# SCH_SmartOEEBoard_2023-07-03.net
KiCad netlist of a schematic drawn in EasyEDA
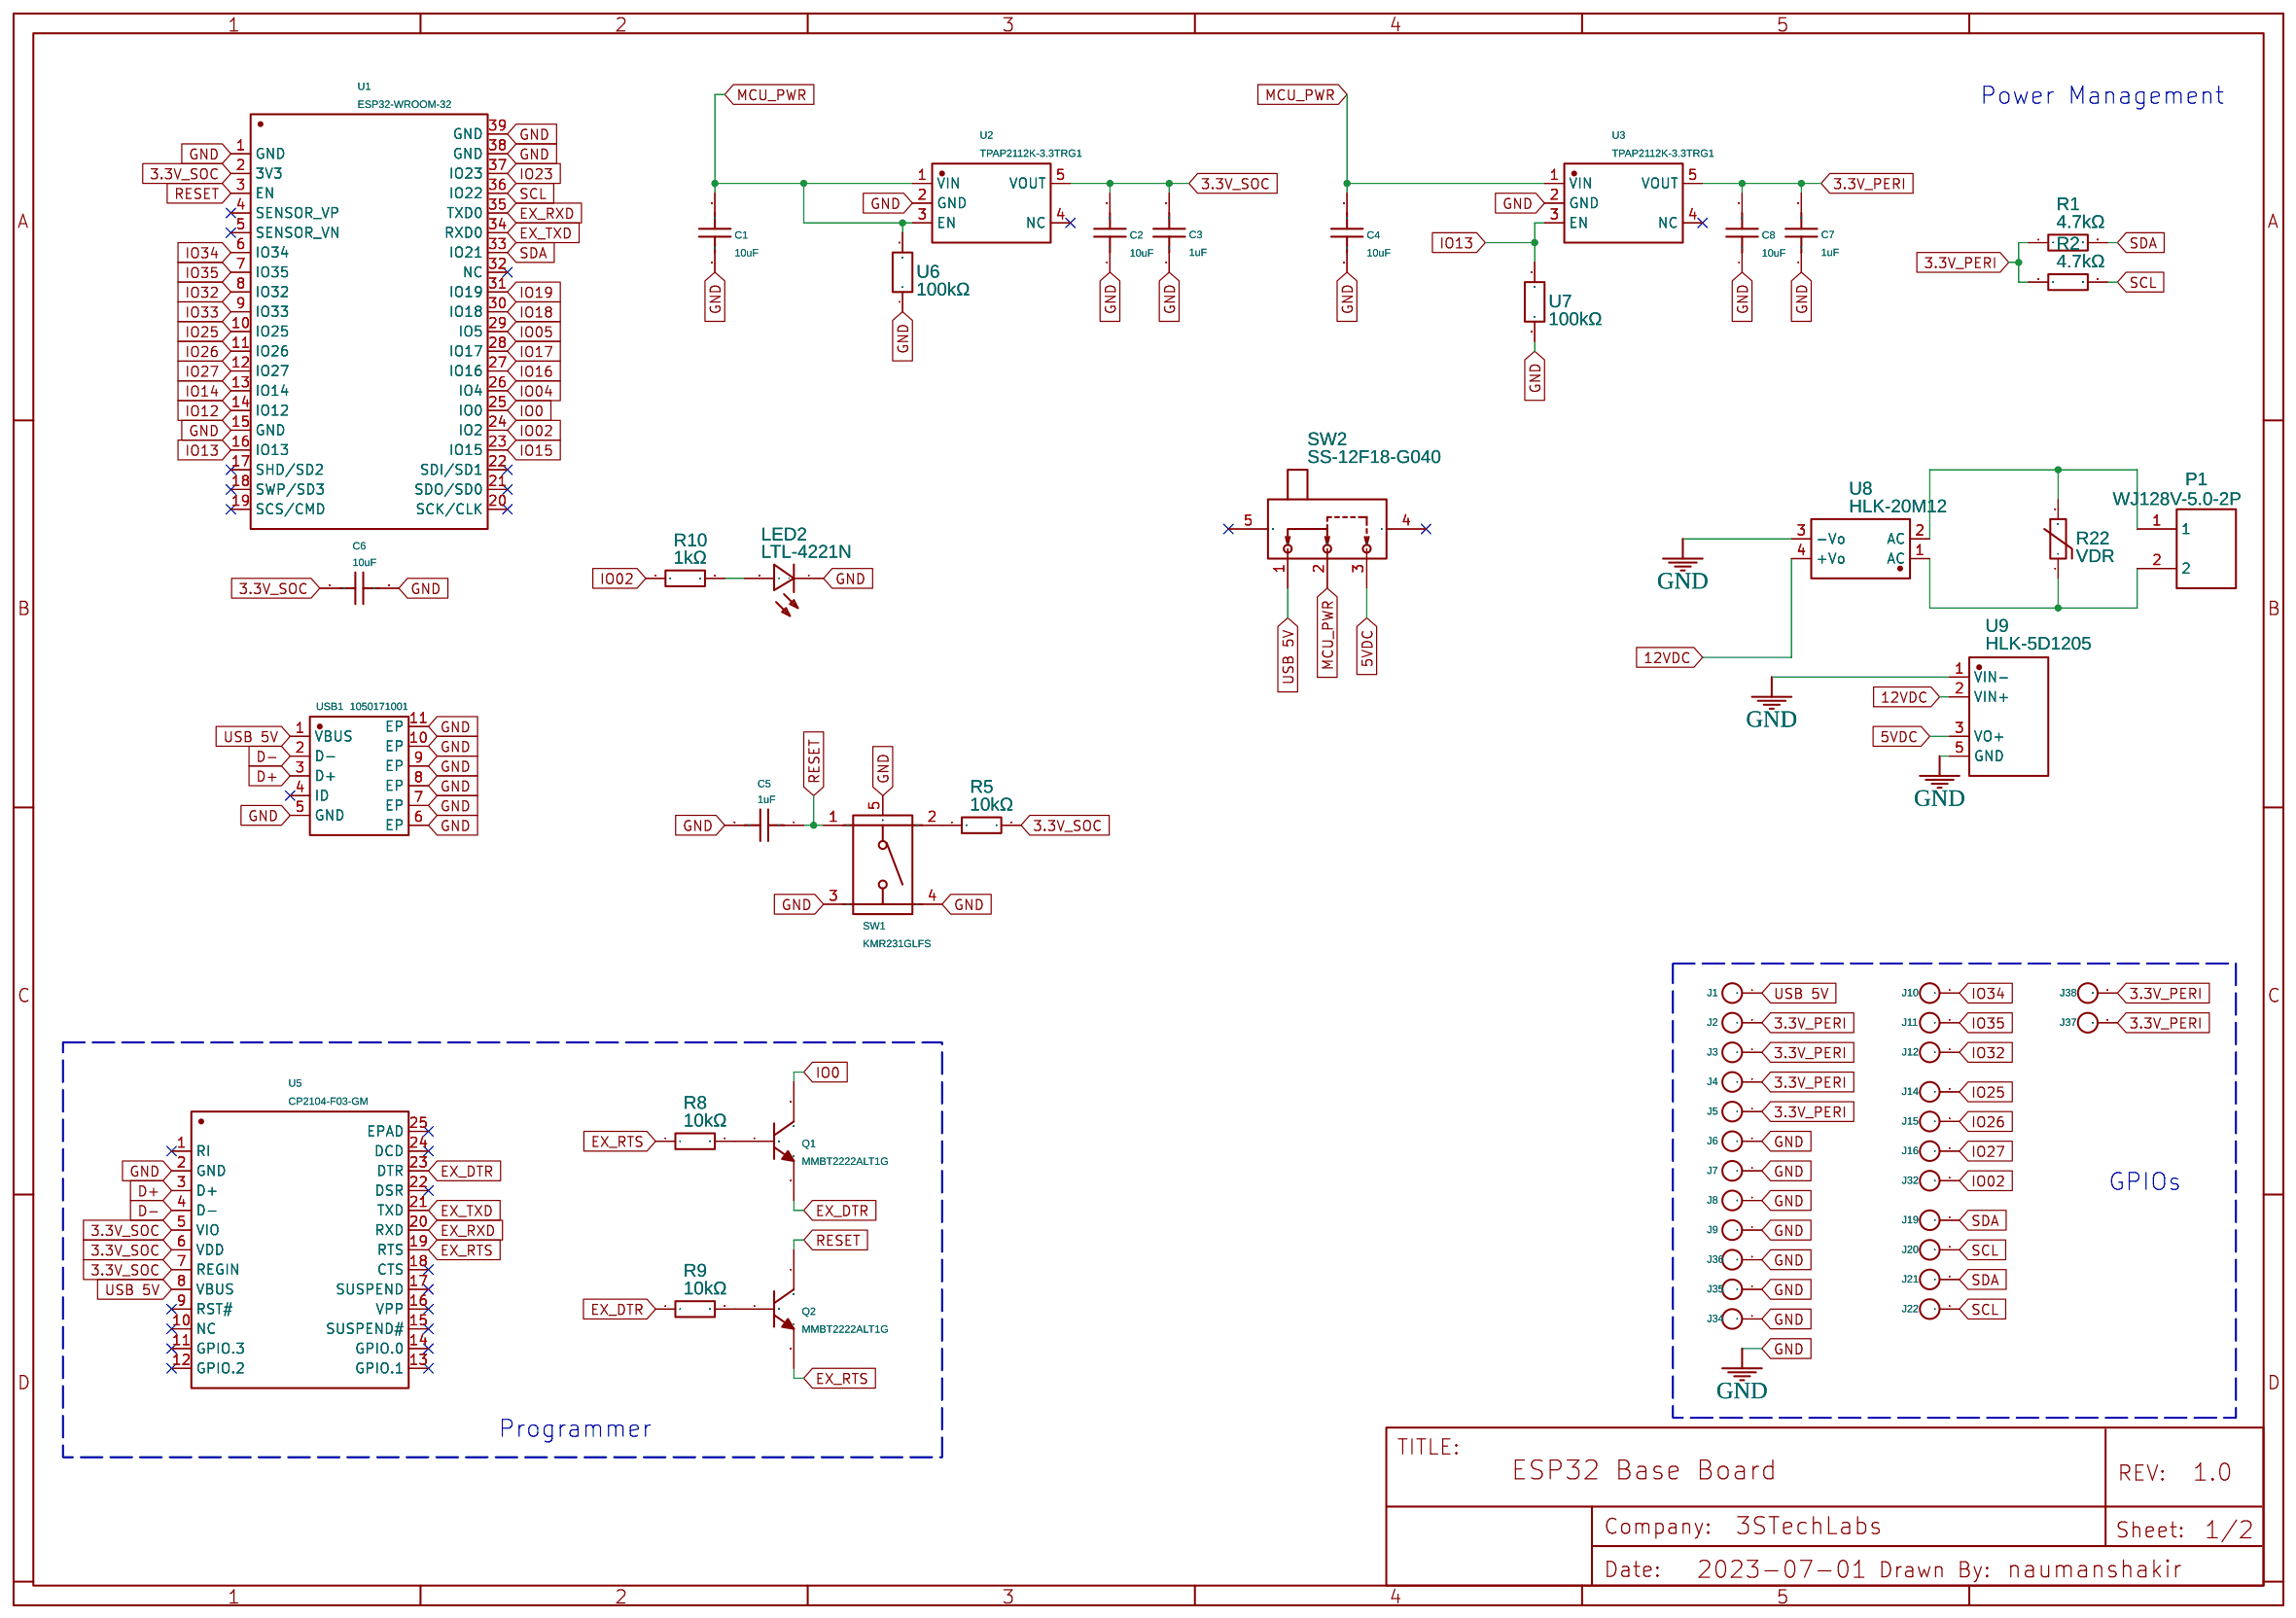
[diagram p0: Sheet_1]
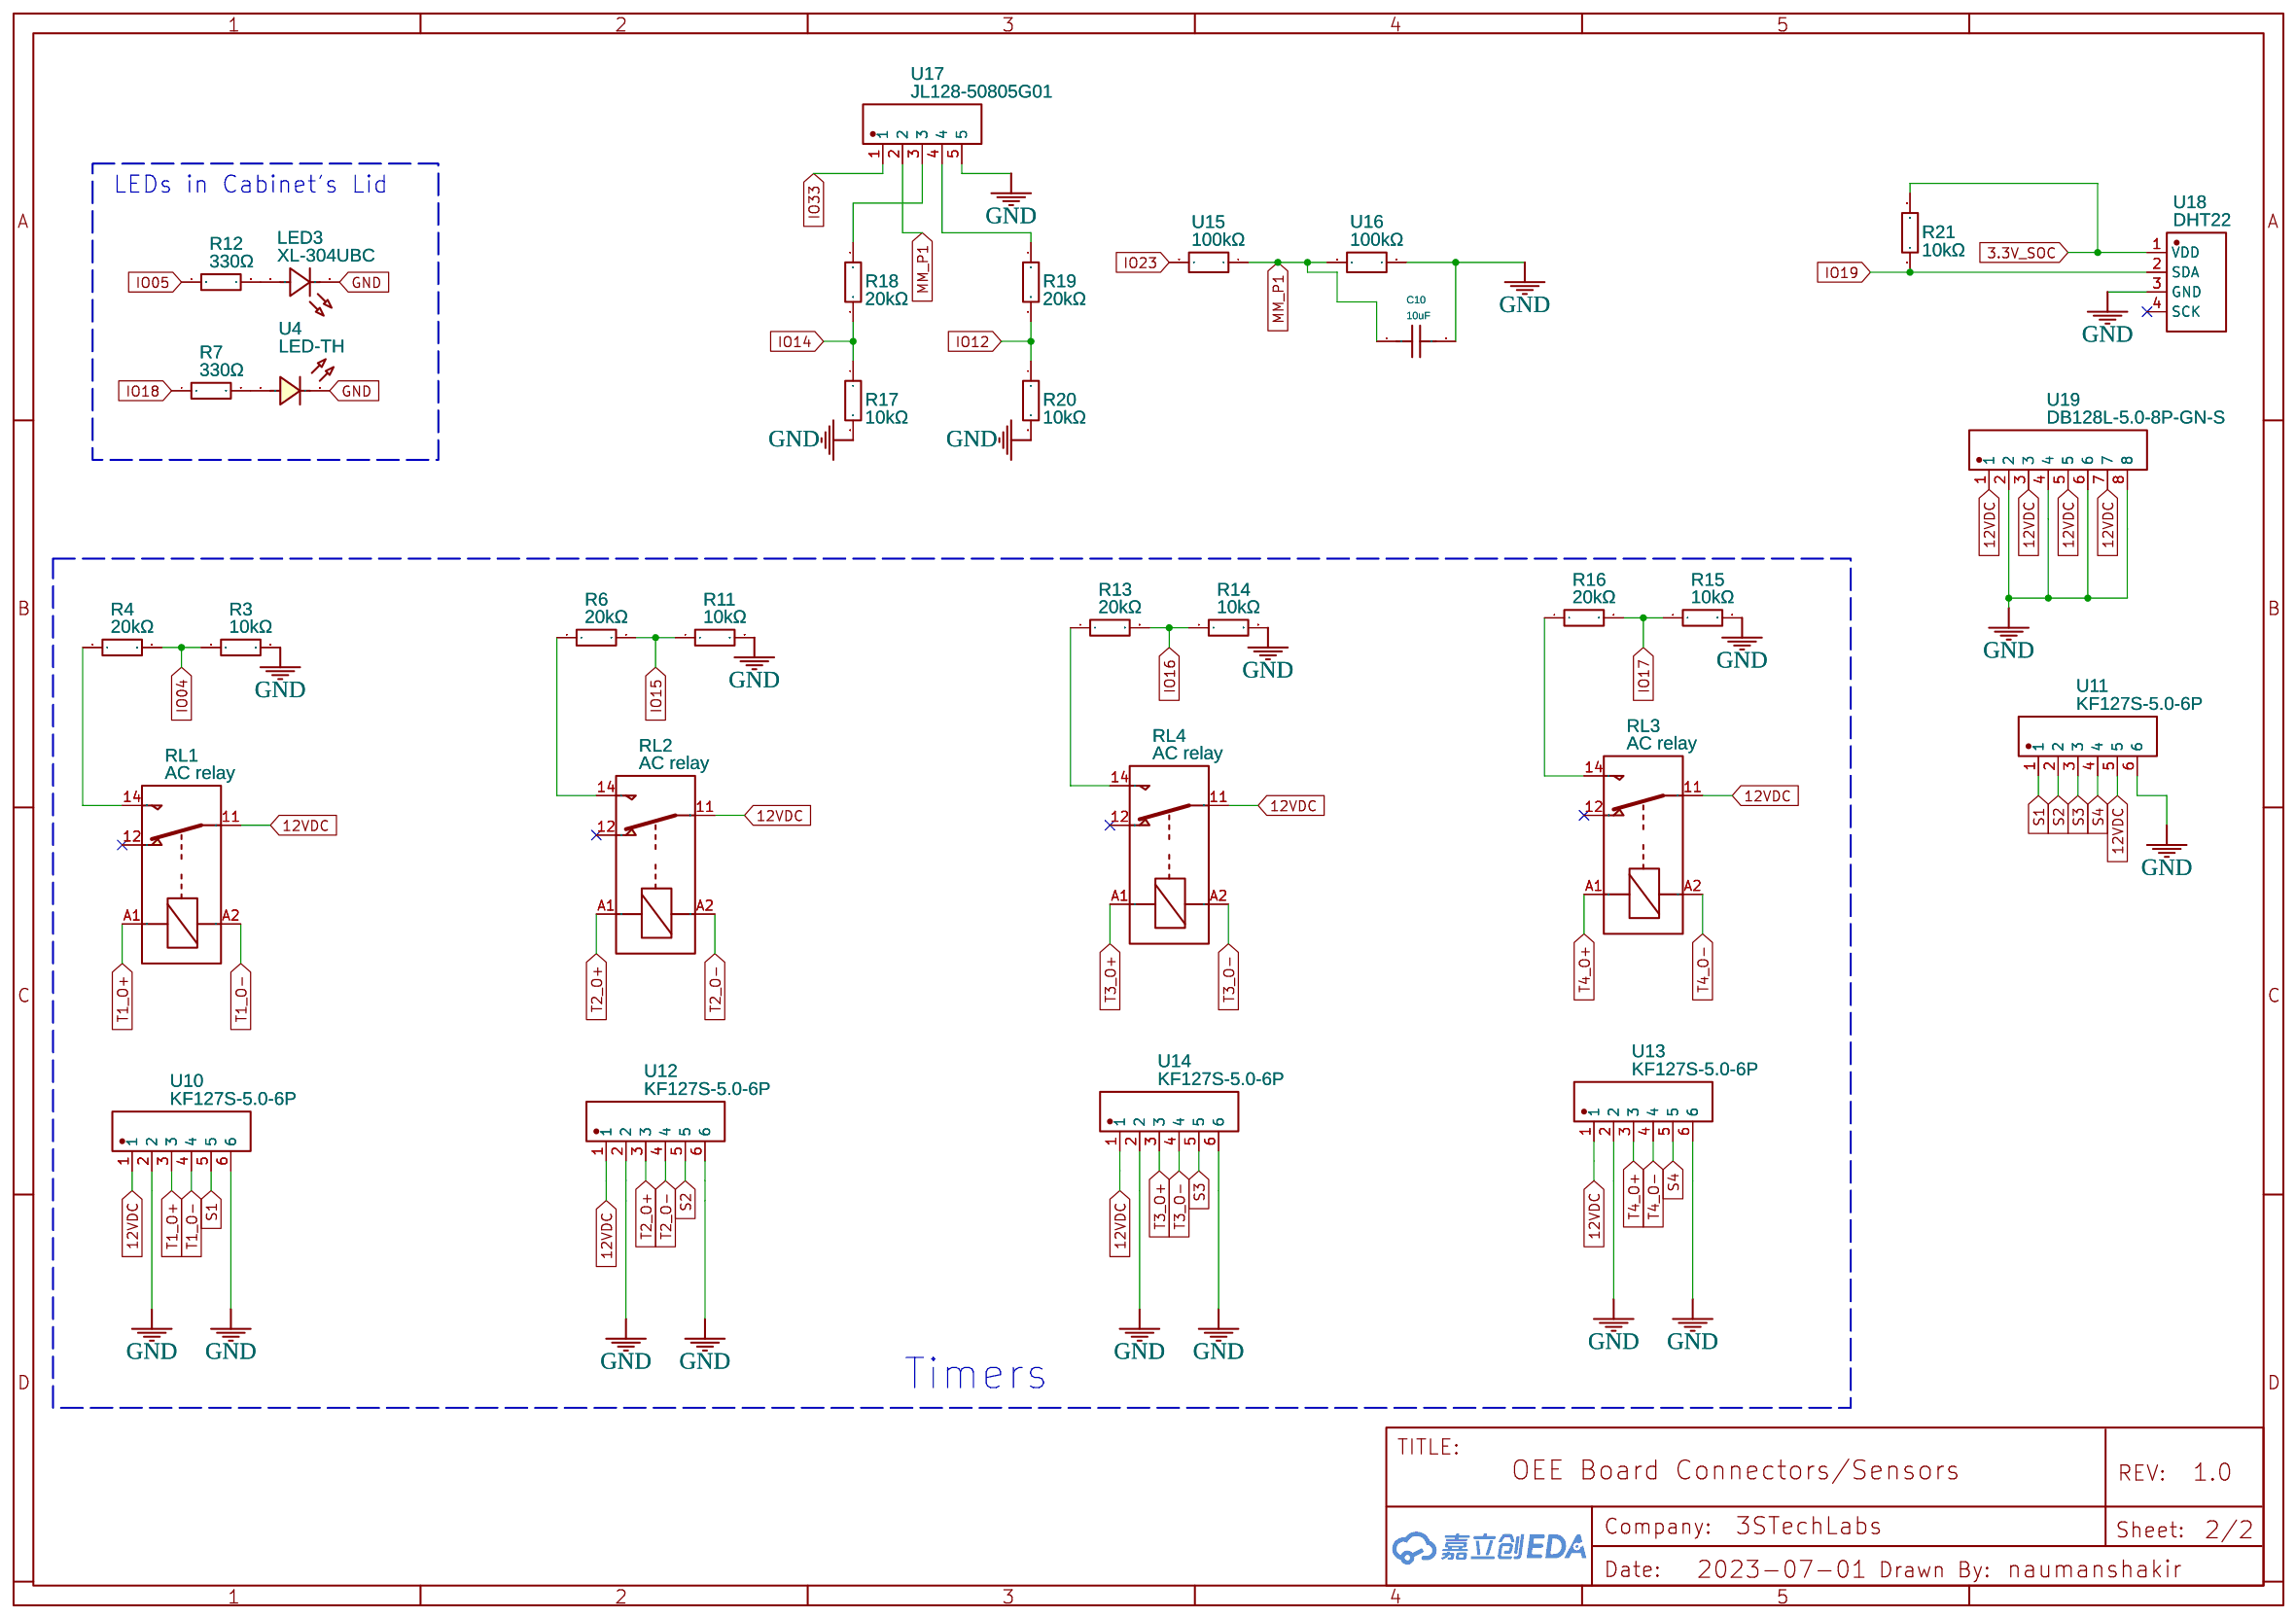
[diagram p1: Sheet_2]

(export (version "E")
  (design (tool "Eeschema 10.0.6"))
  (components
    (comp (ref "C1")
      (value "10uF")
      (fields
        (field (name "BOM_Manufacturer Part") "0603X106K100CT")
        (field (name "BOM_Supplier Part") "C2840513")
      )
      (libsource (lib "") (part "0603X106K100CT"))
    )
    (comp (ref "C2")
      (value "10uF")
      (fields
        (field (name "BOM_Manufacturer Part") "C0603X5R106M160NT")
        (field (name "BOM_Supplier Part") "C466781")
      )
      (libsource (lib "") (part "C0603X5R106M160NT_1"))
    )
    (comp (ref "C3")
      (value "1uF")
      (fields
        (field (name "BOM_Manufacturer Part") "CC0603KRX7R6BB105")
        (field (name "BOM_Supplier Part") "C113807")
      )
      (libsource (lib "") (part "CC0603KRX7R6BB105_1"))
    )
    (comp (ref "C4")
      (value "10uF")
      (fields
        (field (name "BOM_Manufacturer Part") "0603X106K100CT")
        (field (name "BOM_Supplier Part") "C2840513")
      )
      (libsource (lib "") (part "0603X106K100CT"))
    )
    (comp (ref "C5")
      (value "1uF")
      (fields
        (field (name "BOM_Manufacturer Part") "CC0603KRX7R6BB105")
        (field (name "BOM_Supplier Part") "C113807")
      )
      (libsource (lib "") (part "CC0603KRX7R6BB105"))
    )
    (comp (ref "C6")
      (value "10uF")
      (fields
        (field (name "BOM_Manufacturer Part") "C0603X5R106M160NT")
        (field (name "BOM_Supplier Part") "C466781")
      )
      (libsource (lib "") (part "C0603X5R106M160NT"))
    )
    (comp (ref "C7")
      (value "1uF")
      (fields
        (field (name "BOM_Manufacturer Part") "CC0603KRX7R6BB105")
        (field (name "BOM_Supplier Part") "C113807")
      )
      (libsource (lib "") (part "CC0603KRX7R6BB105_1"))
    )
    (comp (ref "C8")
      (value "10uF")
      (fields
        (field (name "BOM_Manufacturer Part") "C0603X5R106M160NT")
        (field (name "BOM_Supplier Part") "C466781")
      )
      (libsource (lib "") (part "C0603X5R106M160NT_1"))
    )
    (comp (ref "J1") (value "THT Pad") (libsource (lib "") (part "THT Pad")))
    (comp (ref "J2") (value "THT Pad") (libsource (lib "") (part "THT Pad")))
    (comp (ref "J3") (value "THT Pad") (libsource (lib "") (part "THT Pad")))
    (comp (ref "J4") (value "THT Pad") (libsource (lib "") (part "THT Pad")))
    (comp (ref "J5") (value "THT Pad") (libsource (lib "") (part "THT Pad")))
    (comp (ref "J6") (value "THT Pad") (libsource (lib "") (part "THT Pad")))
    (comp (ref "J7") (value "THT Pad") (libsource (lib "") (part "THT Pad")))
    (comp (ref "J8") (value "THT Pad") (libsource (lib "") (part "THT Pad")))
    (comp (ref "J9") (value "THT Pad") (libsource (lib "") (part "THT Pad")))
    (comp (ref "J10") (value "THT Pad") (libsource (lib "") (part "THT Pad")))
    (comp (ref "J11") (value "THT Pad") (libsource (lib "") (part "THT Pad")))
    (comp (ref "J12") (value "THT Pad") (libsource (lib "") (part "THT Pad")))
    (comp (ref "J14") (value "THT Pad") (libsource (lib "") (part "THT Pad")))
    (comp (ref "J15") (value "THT Pad") (libsource (lib "") (part "THT Pad")))
    (comp (ref "J16") (value "THT Pad") (libsource (lib "") (part "THT Pad")))
    (comp (ref "J19") (value "THT Pad") (libsource (lib "") (part "THT Pad")))
    (comp (ref "J20") (value "THT Pad") (libsource (lib "") (part "THT Pad")))
    (comp (ref "J21") (value "THT Pad") (libsource (lib "") (part "THT Pad")))
    (comp (ref "J22") (value "THT Pad") (libsource (lib "") (part "THT Pad")))
    (comp (ref "J32") (value "THT Pad") (libsource (lib "") (part "THT Pad")))
    (comp (ref "J34") (value "THT Pad") (libsource (lib "") (part "THT Pad")))
    (comp (ref "J35") (value "THT Pad") (libsource (lib "") (part "THT Pad")))
    (comp (ref "J36") (value "THT Pad") (libsource (lib "") (part "THT Pad")))
    (comp (ref "J37") (value "THT Pad") (libsource (lib "") (part "THT Pad")))
    (comp (ref "J38") (value "THT Pad") (libsource (lib "") (part "THT Pad")))
    (comp (ref "LED2")
      (value "LTL-4221N")
      (fields (field (name "BOM_Supplier Part") "C125081"))
      (libsource (lib "") (part "LTL-4221N"))
    )
    (comp (ref "P1")
      (value "WJ128V-5.0-2P")
      (fields (field (name "BOM_Supplier Part") "C8269"))
      (libsource (lib "") (part "WJ128V-5.0-2P"))
    )
    (comp (ref "Q1")
      (value "MMBT2222ALT1G")
      (fields (field (name "BOM_Supplier Part") "C82460"))
      (libsource (lib "") (part "MMBT2222ALT1G"))
    )
    (comp (ref "Q2")
      (value "MMBT2222ALT1G")
      (fields (field (name "BOM_Supplier Part") "C82460"))
      (libsource (lib "") (part "MMBT2222ALT1G"))
    )
    (comp (ref "R1")
      (value "4.7kΩ")
      (fields
        (field (name "BOM_Manufacturer Part") "CF1/4W-4.7KΩ±5% T")
        (field (name "BOM_Supplier Part") "C120071")
      )
      (libsource (lib "") (part "CF1/4W-4.7KΩ±5% T52"))
    )
    (comp (ref "R2")
      (value "4.7kΩ")
      (fields
        (field (name "BOM_Manufacturer Part") "CF1/4W-4.7KΩ±5% T")
        (field (name "BOM_Supplier Part") "C120071")
      )
      (libsource (lib "") (part "CF1/4W-4.7KΩ±5% T52"))
    )
    (comp (ref "R5")
      (value "10kΩ")
      (fields
        (field (name "BOM_Manufacturer Part") "MF1/4W-10KΩ±1% T")
        (field (name "BOM_Supplier Part") "C119347")
      )
      (libsource (lib "") (part "MF1/4W-10KΩ±1% T52"))
    )
    (comp (ref "R8")
      (value "10kΩ")
      (fields
        (field (name "BOM_Manufacturer Part") "MF1/4W-10KΩ±1% T")
        (field (name "BOM_Supplier Part") "C119347")
      )
      (libsource (lib "") (part "MF1/4W-10KΩ±1% T52"))
    )
    (comp (ref "R9")
      (value "10kΩ")
      (fields
        (field (name "BOM_Manufacturer Part") "MF1/4W-10KΩ±1% T")
        (field (name "BOM_Supplier Part") "C119347")
      )
      (libsource (lib "") (part "MF1/4W-10KΩ±1% T52"))
    )
    (comp (ref "R10")
      (value "1kΩ")
      (fields
        (field (name "BOM_Manufacturer Part") "CF1/4W-1KΩ±5% T")
        (field (name "BOM_Supplier Part") "C120055")
      )
      (libsource (lib "") (part "CF1/4W-1KΩ±5% T52"))
    )
    (comp (ref "R22")
      (value "VDR")
      (fields
        (field (name "BOM_Manufacturer Part") "VDR-07D241K")
        (field (name "BOM_Supplier Part") "C283926")
      )
      (libsource (lib "") (part "VDR-07D241K"))
    )
    (comp (ref "SW1")
      (value "KMR231GLFS")
      (fields (field (name "BOM_Supplier Part") "C99271"))
      (libsource (lib "") (part "KMR231GLFS"))
    )
    (comp (ref "SW2")
      (value "SS-12F18-G040")
      (fields (field (name "BOM_Supplier Part") "C2848918"))
      (libsource (lib "") (part "SS-12F18-G040"))
    )
    (comp (ref "U1")
      (value "ESP32-WROOM-32")
      (fields
        (field (name "BOM_Manufacturer Part") "ESP32-WROOM-32-N4")
        (field (name "BOM_Supplier Part") "C82899")
      )
      (libsource (lib "") (part "ESP32-WROOM-32"))
    )
    (comp (ref "U2")
      (value "TPAP2112K-3.3TRG1")
      (fields (field (name "BOM_Supplier Part") "C3021085"))
      (libsource (lib "") (part "TPAP2112K-3.3TRG1"))
    )
    (comp (ref "U3")
      (value "TPAP2112K-3.3TRG1")
      (fields (field (name "BOM_Supplier Part") "C3021085"))
      (libsource (lib "") (part "TPAP2112K-3.3TRG1"))
    )
    (comp (ref "U5")
      (value "CP2104-F03-GM")
      (fields
        (field (name "BOM_Manufacturer Part") "CP2104-F03-GMR")
        (field (name "BOM_Supplier Part") "C47742")
      )
      (libsource (lib "") (part "CP2104-F03-GM"))
    )
    (comp (ref "U6")
      (value "100kΩ")
      (fields
        (field (name "BOM_Manufacturer Part") "RI40-1/4W-100KΩ±1%T")
        (field (name "BOM_Supplier Part") "C714626")
      )
      (libsource (lib "") (part "RI40-1/4W-100KΩ±1%T"))
    )
    (comp (ref "U7")
      (value "100kΩ")
      (fields
        (field (name "BOM_Manufacturer Part") "RI40-1/4W-100KΩ±1%T")
        (field (name "BOM_Supplier Part") "C714626")
      )
      (libsource (lib "") (part "RI40-1/4W-100KΩ±1%T"))
    )
    (comp (ref "U8")
      (value "HLK-20M12")
      (fields (field (name "BOM_Supplier Part") "C465408"))
      (libsource (lib "") (part "HLK-20M12"))
    )
    (comp (ref "U9")
      (value "HLK-5D1205")
      (fields (field (name "BOM_Supplier Part") "C474033"))
      (libsource (lib "") (part "HLK-5D1205"))
    )
    (comp (ref "USB1")
      (value "1050171001")
      (fields (field (name "BOM_Supplier Part") "C505111"))
      (libsource (lib "") (part "1050171001"))
    )
    (comp (ref "C10")
      (value "10uF")
      (fields
        (field (name "BOM_Manufacturer Part") "0603X106K100CT")
        (field (name "BOM_Supplier Part") "C2840513")
      )
      (libsource (lib "") (part "0603X106K100CT"))
    )
    (comp (ref "LED3")
      (value "XL-304UBC")
      (fields (field (name "BOM_Supplier Part") "C2895465"))
      (libsource (lib "") (part "XL-304UBC"))
    )
    (comp (ref "R3")
      (value "10kΩ")
      (fields
        (field (name "BOM_Manufacturer Part") "MF1/4W-10KΩ±1% T")
        (field (name "BOM_Supplier Part") "C119347")
      )
      (libsource (lib "") (part "MF1/4W-10KΩ±1% T52_2"))
    )
    (comp (ref "R4")
      (value "20kΩ")
      (fields
        (field (name "BOM_Manufacturer Part") "CF1/4W-20KΩ±5% T")
        (field (name "BOM_Supplier Part") "C120086")
      )
      (libsource (lib "") (part "CF1/4W-20KΩ±5% T52"))
    )
    (comp (ref "R6")
      (value "20kΩ")
      (fields
        (field (name "BOM_Manufacturer Part") "CF1/4W-20KΩ±5% T")
        (field (name "BOM_Supplier Part") "C120086")
      )
      (libsource (lib "") (part "CF1/4W-20KΩ±5% T52"))
    )
    (comp (ref "R7")
      (value "330Ω")
      (fields
        (field (name "BOM_Manufacturer Part") "MF1/4CCT52A3300F")
        (field (name "BOM_Supplier Part") "C315657")
      )
      (libsource (lib "") (part "MF1/4CCT52A3300F"))
    )
    (comp (ref "R11")
      (value "10kΩ")
      (fields
        (field (name "BOM_Manufacturer Part") "MF1/4W-10KΩ±1% T")
        (field (name "BOM_Supplier Part") "C119347")
      )
      (libsource (lib "") (part "MF1/4W-10KΩ±1% T52_2"))
    )
    (comp (ref "R12")
      (value "330Ω")
      (fields
        (field (name "BOM_Manufacturer Part") "MF1/4CCT52A3300F")
        (field (name "BOM_Supplier Part") "C315657")
      )
      (libsource (lib "") (part "MF1/4CCT52A3300F"))
    )
    (comp (ref "R13")
      (value "20kΩ")
      (fields
        (field (name "BOM_Manufacturer Part") "CF1/4W-20KΩ±5% T")
        (field (name "BOM_Supplier Part") "C120086")
      )
      (libsource (lib "") (part "CF1/4W-20KΩ±5% T52"))
    )
    (comp (ref "R14")
      (value "10kΩ")
      (fields
        (field (name "BOM_Manufacturer Part") "MF1/4W-10KΩ±1% T")
        (field (name "BOM_Supplier Part") "C119347")
      )
      (libsource (lib "") (part "MF1/4W-10KΩ±1% T52_2"))
    )
    (comp (ref "R15")
      (value "10kΩ")
      (fields
        (field (name "BOM_Manufacturer Part") "MF1/4W-10KΩ±1% T")
        (field (name "BOM_Supplier Part") "C119347")
      )
      (libsource (lib "") (part "MF1/4W-10KΩ±1% T52_2"))
    )
    (comp (ref "R16")
      (value "20kΩ")
      (fields
        (field (name "BOM_Manufacturer Part") "CF1/4W-20KΩ±5% T")
        (field (name "BOM_Supplier Part") "C120086")
      )
      (libsource (lib "") (part "CF1/4W-20KΩ±5% T52"))
    )
    (comp (ref "R17")
      (value "10kΩ")
      (fields
        (field (name "BOM_Manufacturer Part") "MF1/4W-10KΩ±1% T")
        (field (name "BOM_Supplier Part") "C119347")
      )
      (libsource (lib "") (part "MF1/4W-10KΩ±1% T52_1"))
    )
    (comp (ref "R18")
      (value "20kΩ")
      (fields
        (field (name "BOM_Manufacturer Part") "CF1/4W-20KΩ±5% T")
        (field (name "BOM_Supplier Part") "C120086")
      )
      (libsource (lib "") (part "CF1/4W-20KΩ±5% T52_1"))
    )
    (comp (ref "R19")
      (value "20kΩ")
      (fields
        (field (name "BOM_Manufacturer Part") "CF1/4W-20KΩ±5% T")
        (field (name "BOM_Supplier Part") "C120086")
      )
      (libsource (lib "") (part "CF1/4W-20KΩ±5% T52_1"))
    )
    (comp (ref "R20")
      (value "10kΩ")
      (fields
        (field (name "BOM_Manufacturer Part") "MF1/4W-10KΩ±1% T")
        (field (name "BOM_Supplier Part") "C119347")
      )
      (libsource (lib "") (part "MF1/4W-10KΩ±1% T52_1"))
    )
    (comp (ref "R21")
      (value "10kΩ")
      (fields
        (field (name "BOM_Manufacturer Part") "MF1/4W-10KΩ±1% T")
        (field (name "BOM_Supplier Part") "C119347")
      )
      (libsource (lib "") (part "MF1/4W-10KΩ±1% T52"))
    )
    (comp (ref "RL1") (value "AC relay") (libsource (lib "") (part "AC relay")))
    (comp (ref "RL2") (value "AC relay") (libsource (lib "") (part "AC relay")))
    (comp (ref "RL3") (value "AC relay") (libsource (lib "") (part "AC relay")))
    (comp (ref "RL4") (value "AC relay") (libsource (lib "") (part "AC relay")))
    (comp (ref "U4")
      (value "LED-TH")
      (fields
        (field (name "BOM_Manufacturer Part") "绿发翠绿φ3直插长脚28mm")
        (field (name "BOM_Supplier Part") "C9900001201")
      )
      (libsource (lib "") (part "LED-TH"))
    )
    (comp (ref "U10")
      (value "KF127S-5.0-6P")
      (fields (field (name "BOM_Supplier Part") "C2974921"))
      (libsource (lib "") (part "KF127S-5.0-6P"))
    )
    (comp (ref "U11")
      (value "KF127S-5.0-6P")
      (fields (field (name "BOM_Supplier Part") "C2974921"))
      (libsource (lib "") (part "KF127S-5.0-6P"))
    )
    (comp (ref "U12")
      (value "KF127S-5.0-6P")
      (fields (field (name "BOM_Supplier Part") "C2974921"))
      (libsource (lib "") (part "KF127S-5.0-6P"))
    )
    (comp (ref "U13")
      (value "KF127S-5.0-6P")
      (fields (field (name "BOM_Supplier Part") "C2974921"))
      (libsource (lib "") (part "KF127S-5.0-6P"))
    )
    (comp (ref "U14")
      (value "KF127S-5.0-6P")
      (fields (field (name "BOM_Supplier Part") "C2974921"))
      (libsource (lib "") (part "KF127S-5.0-6P"))
    )
    (comp (ref "U15")
      (value "100kΩ")
      (fields
        (field (name "BOM_Manufacturer Part") "RI40-1/4W-100KΩ±1%T")
        (field (name "BOM_Supplier Part") "C714626")
      )
      (libsource (lib "") (part "RI40-1/4W-100KΩ±1%T"))
    )
    (comp (ref "U16")
      (value "100kΩ")
      (fields
        (field (name "BOM_Manufacturer Part") "RI40-1/4W-100KΩ±1%T")
        (field (name "BOM_Supplier Part") "C714626")
      )
      (libsource (lib "") (part "RI40-1/4W-100KΩ±1%T"))
    )
    (comp (ref "U17")
      (value "JL128-50805G01")
      (fields (field (name "BOM_Supplier Part") "C2961928"))
      (libsource (lib "") (part "JL128-50805G01"))
    )
    (comp (ref "U18")
      (value "DHT22")
      (fields (field (name "BOM_Supplier Part") "C2880291"))
      (libsource (lib "") (part "DHT22"))
    )
    (comp (ref "U19")
      (value "DB128L-5.0-8P-GN-S")
      (fields (field (name "BOM_Supplier Part") "C430596"))
      (libsource (lib "") (part "DB128L-5.0-8P-GN-S"))
    )
  )
  (nets
    (net (code "1") (name "3.3V_PERI") (class "Default")
      (node (ref "C7") (pin "2") (pinfunction "2_2") (pintype "unspecified"))
      (node (ref "C8") (pin "2") (pinfunction "2_2") (pintype "unspecified"))
      (node (ref "J2") (pin "1") (pinfunction "1_1") (pintype "unspecified"))
      (node (ref "J3") (pin "1") (pinfunction "1_1") (pintype "unspecified"))
      (node (ref "J37") (pin "1") (pinfunction "1_1") (pintype "unspecified"))
      (node (ref "J38") (pin "1") (pinfunction "1_1") (pintype "unspecified"))
      (node (ref "J4") (pin "1") (pinfunction "1_1") (pintype "unspecified"))
      (node (ref "J5") (pin "1") (pinfunction "1_1") (pintype "unspecified"))
      (node (ref "R1") (pin "1") (pinfunction "1_1") (pintype "unspecified"))
      (node (ref "R2") (pin "1") (pinfunction "1_1") (pintype "unspecified"))
      (node (ref "U3") (pin "5") (pinfunction "VOUT_5") (pintype "unspecified"))
    )
    (net (code "2") (name "3.3V_SOC") (class "Default")
      (node (ref "C2") (pin "2") (pinfunction "2_2") (pintype "unspecified"))
      (node (ref "C3") (pin "2") (pinfunction "2_2") (pintype "unspecified"))
      (node (ref "C6") (pin "2") (pinfunction "2_2") (pintype "unspecified"))
      (node (ref "R21") (pin "2") (pinfunction "2_2") (pintype "unspecified"))
      (node (ref "R5") (pin "2") (pinfunction "2_2") (pintype "unspecified"))
      (node (ref "U1") (pin "2") (pinfunction "3V3_2") (pintype "unspecified"))
      (node (ref "U18") (pin "1") (pinfunction "VDD_1") (pintype "unspecified"))
      (node (ref "U2") (pin "5") (pinfunction "VOUT_5") (pintype "unspecified"))
      (node (ref "U5") (pin "5") (pinfunction "VIO_5") (pintype "unspecified"))
      (node (ref "U5") (pin "6") (pinfunction "VDD_6") (pintype "unspecified"))
      (node (ref "U5") (pin "7") (pinfunction "REGIN_7") (pintype "unspecified"))
    )
    (net (code "3") (name "5VDC") (class "Default")
      (node (ref "SW2") (pin "3") (pinfunction "3_3") (pintype "unspecified"))
      (node (ref "U9") (pin "3") (pinfunction "VO+_3") (pintype "unspecified"))
    )
    (net (code "4") (name "12VDC") (class "Default")
      (node (ref "RL1") (pin "11") (pinfunction "11_11") (pintype "unspecified"))
      (node (ref "RL2") (pin "11") (pinfunction "11_11") (pintype "unspecified"))
      (node (ref "RL3") (pin "11") (pinfunction "11_11") (pintype "unspecified"))
      (node (ref "RL4") (pin "11") (pinfunction "11_11") (pintype "unspecified"))
      (node (ref "U10") (pin "1") (pinfunction "1_1") (pintype "unspecified"))
      (node (ref "U11") (pin "5") (pinfunction "5_5") (pintype "unspecified"))
      (node (ref "U12") (pin "1") (pinfunction "1_1") (pintype "unspecified"))
      (node (ref "U13") (pin "1") (pinfunction "1_1") (pintype "unspecified"))
      (node (ref "U14") (pin "1") (pinfunction "1_1") (pintype "unspecified"))
      (node (ref "U19") (pin "1") (pinfunction "1_1") (pintype "unspecified"))
      (node (ref "U19") (pin "3") (pinfunction "3_3") (pintype "unspecified"))
      (node (ref "U19") (pin "5") (pinfunction "5_5") (pintype "unspecified"))
      (node (ref "U19") (pin "7") (pinfunction "7_7") (pintype "unspecified"))
      (node (ref "U8") (pin "4") (pinfunction "+Vo_4") (pintype "unspecified"))
      (node (ref "U9") (pin "2") (pinfunction "VIN+_2") (pintype "unspecified"))
    )
    (net (code "5") (name "D+") (class "Default")
      (node (ref "U5") (pin "3") (pinfunction "D+_3") (pintype "unspecified"))
      (node (ref "USB1") (pin "3") (pinfunction "D+_3") (pintype "unspecified"))
    )
    (net (code "6") (name "D-") (class "Default")
      (node (ref "U5") (pin "4") (pinfunction "D-_4") (pintype "unspecified"))
      (node (ref "USB1") (pin "2") (pinfunction "D-_2") (pintype "unspecified"))
    )
    (net (code "7") (name "EX_DTR") (class "Default")
      (node (ref "Q1") (pin "2") (pinfunction "E_2") (pintype "unspecified"))
      (node (ref "R9") (pin "1") (pinfunction "1_1") (pintype "unspecified"))
      (node (ref "U5") (pin "23") (pinfunction "DTR_23") (pintype "unspecified"))
    )
    (net (code "8") (name "EX_RTS") (class "Default")
      (node (ref "Q2") (pin "2") (pinfunction "E_2") (pintype "unspecified"))
      (node (ref "R8") (pin "1") (pinfunction "1_1") (pintype "unspecified"))
      (node (ref "U5") (pin "19") (pinfunction "RTS_19") (pintype "unspecified"))
    )
    (net (code "9") (name "EX_RXD") (class "Default")
      (node (ref "U1") (pin "35") (pinfunction "TXD0_35") (pintype "unspecified"))
      (node (ref "U5") (pin "20") (pinfunction "RXD_20") (pintype "unspecified"))
    )
    (net (code "10") (name "EX_TXD") (class "Default")
      (node (ref "U1") (pin "34") (pinfunction "RXD0_34") (pintype "unspecified"))
      (node (ref "U5") (pin "21") (pinfunction "TXD_21") (pintype "unspecified"))
    )
    (net (code "11") (name "GND") (class "Default")
      (node (ref "C1") (pin "2") (pinfunction "2_2") (pintype "unspecified"))
      (node (ref "C10") (pin "2") (pinfunction "2_2") (pintype "unspecified"))
      (node (ref "C2") (pin "1") (pinfunction "1_1") (pintype "unspecified"))
      (node (ref "C3") (pin "1") (pinfunction "1_1") (pintype "unspecified"))
      (node (ref "C4") (pin "2") (pinfunction "2_2") (pintype "unspecified"))
      (node (ref "C5") (pin "2") (pinfunction "2_2") (pintype "unspecified"))
      (node (ref "C6") (pin "1") (pinfunction "1_1") (pintype "unspecified"))
      (node (ref "C7") (pin "1") (pinfunction "1_1") (pintype "unspecified"))
      (node (ref "C8") (pin "1") (pinfunction "1_1") (pintype "unspecified"))
      (node (ref "J34") (pin "1") (pinfunction "1_1") (pintype "unspecified"))
      (node (ref "J35") (pin "1") (pinfunction "1_1") (pintype "unspecified"))
      (node (ref "J36") (pin "1") (pinfunction "1_1") (pintype "unspecified"))
      (node (ref "J6") (pin "1") (pinfunction "1_1") (pintype "unspecified"))
      (node (ref "J7") (pin "1") (pinfunction "1_1") (pintype "unspecified"))
      (node (ref "J8") (pin "1") (pinfunction "1_1") (pintype "unspecified"))
      (node (ref "J9") (pin "1") (pinfunction "1_1") (pintype "unspecified"))
      (node (ref "LED2") (pin "1") (pinfunction "-_1") (pintype "unspecified"))
      (node (ref "LED3") (pin "2") (pinfunction "K_2") (pintype "unspecified"))
      (node (ref "R11") (pin "2") (pinfunction "2_2") (pintype "unspecified"))
      (node (ref "R14") (pin "2") (pinfunction "2_2") (pintype "unspecified"))
      (node (ref "R15") (pin "2") (pinfunction "2_2") (pintype "unspecified"))
      (node (ref "R17") (pin "2") (pinfunction "2_2") (pintype "unspecified"))
      (node (ref "R20") (pin "2") (pinfunction "2_2") (pintype "unspecified"))
      (node (ref "R3") (pin "2") (pinfunction "2_2") (pintype "unspecified"))
      (node (ref "SW1") (pin "3") (pinfunction "3_3") (pintype "unspecified"))
      (node (ref "SW1") (pin "4") (pinfunction "4_4") (pintype "unspecified"))
      (node (ref "SW1") (pin "5") (pinfunction "5_5") (pintype "unspecified"))
      (node (ref "U1") (pin "1") (pinfunction "GND_1") (pintype "unspecified"))
      (node (ref "U1") (pin "15") (pinfunction "GND_15") (pintype "unspecified"))
      (node (ref "U1") (pin "38") (pinfunction "GND_38") (pintype "unspecified"))
      (node (ref "U1") (pin "39") (pinfunction "GND_39") (pintype "unspecified"))
      (node (ref "U10") (pin "2") (pinfunction "2_2") (pintype "unspecified"))
      (node (ref "U10") (pin "6") (pinfunction "6_6") (pintype "unspecified"))
      (node (ref "U11") (pin "6") (pinfunction "6_6") (pintype "unspecified"))
      (node (ref "U12") (pin "2") (pinfunction "2_2") (pintype "unspecified"))
      (node (ref "U12") (pin "6") (pinfunction "6_6") (pintype "unspecified"))
      (node (ref "U13") (pin "2") (pinfunction "2_2") (pintype "unspecified"))
      (node (ref "U13") (pin "6") (pinfunction "6_6") (pintype "unspecified"))
      (node (ref "U14") (pin "2") (pinfunction "2_2") (pintype "unspecified"))
      (node (ref "U14") (pin "6") (pinfunction "6_6") (pintype "unspecified"))
      (node (ref "U16") (pin "1") (pinfunction "1_1") (pintype "unspecified"))
      (node (ref "U17") (pin "5") (pinfunction "5_5") (pintype "unspecified"))
      (node (ref "U18") (pin "3") (pinfunction "GND_3") (pintype "unspecified"))
      (node (ref "U19") (pin "2") (pinfunction "2_2") (pintype "unspecified"))
      (node (ref "U19") (pin "4") (pinfunction "4_4") (pintype "unspecified"))
      (node (ref "U19") (pin "6") (pinfunction "6_6") (pintype "unspecified"))
      (node (ref "U19") (pin "8") (pinfunction "8_8") (pintype "unspecified"))
      (node (ref "U2") (pin "2") (pinfunction "GND_2") (pintype "unspecified"))
      (node (ref "U3") (pin "2") (pinfunction "GND_2") (pintype "unspecified"))
      (node (ref "U4") (pin "2") (pinfunction "K_2") (pintype "unspecified"))
      (node (ref "U5") (pin "2") (pinfunction "GND_2") (pintype "unspecified"))
      (node (ref "U6") (pin "1") (pinfunction "1_1") (pintype "unspecified"))
      (node (ref "U7") (pin "1") (pinfunction "1_1") (pintype "unspecified"))
      (node (ref "U8") (pin "3") (pinfunction "-Vo_3") (pintype "unspecified"))
      (node (ref "U9") (pin "1") (pinfunction "VIN-_1") (pintype "unspecified"))
      (node (ref "U9") (pin "5") (pinfunction "GND_5") (pintype "unspecified"))
      (node (ref "USB1") (pin "10") (pinfunction "EP_10") (pintype "unspecified"))
      (node (ref "USB1") (pin "11") (pinfunction "EP_11") (pintype "unspecified"))
      (node (ref "USB1") (pin "5") (pinfunction "GND_5") (pintype "unspecified"))
      (node (ref "USB1") (pin "6") (pinfunction "EP_6") (pintype "unspecified"))
      (node (ref "USB1") (pin "7") (pinfunction "EP_7") (pintype "unspecified"))
      (node (ref "USB1") (pin "8") (pinfunction "EP_8") (pintype "unspecified"))
      (node (ref "USB1") (pin "9") (pinfunction "EP_9") (pintype "unspecified"))
    )
    (net (code "12") (name "IO0") (class "Default")
      (node (ref "Q1") (pin "3") (pinfunction "C_3") (pintype "unspecified"))
      (node (ref "U1") (pin "25") (pinfunction "IO0_25") (pintype "unspecified"))
    )
    (net (code "13") (name "IO02") (class "Default")
      (node (ref "J32") (pin "1") (pinfunction "1_1") (pintype "unspecified"))
      (node (ref "R10") (pin "1") (pinfunction "1_1") (pintype "unspecified"))
      (node (ref "U1") (pin "24") (pinfunction "IO2_24") (pintype "unspecified"))
    )
    (net (code "14") (name "IO04") (class "Default")
      (node (ref "R3") (pin "1") (pinfunction "1_1") (pintype "unspecified"))
      (node (ref "R4") (pin "2") (pinfunction "2_2") (pintype "unspecified"))
      (node (ref "U1") (pin "26") (pinfunction "IO4_26") (pintype "unspecified"))
    )
    (net (code "15") (name "IO05") (class "Default")
      (node (ref "R12") (pin "1") (pinfunction "1_1") (pintype "unspecified"))
      (node (ref "U1") (pin "29") (pinfunction "IO5_29") (pintype "unspecified"))
    )
    (net (code "16") (name "IO12") (class "Default")
      (node (ref "R19") (pin "2") (pinfunction "2_2") (pintype "unspecified"))
      (node (ref "R20") (pin "1") (pinfunction "1_1") (pintype "unspecified"))
      (node (ref "U1") (pin "14") (pinfunction "IO12_14") (pintype "unspecified"))
    )
    (net (code "17") (name "IO13") (class "Default")
      (node (ref "U1") (pin "16") (pinfunction "IO13_16") (pintype "unspecified"))
      (node (ref "U3") (pin "3") (pinfunction "EN_3") (pintype "unspecified"))
      (node (ref "U7") (pin "2") (pinfunction "2_2") (pintype "unspecified"))
    )
    (net (code "18") (name "IO14") (class "Default")
      (node (ref "R17") (pin "1") (pinfunction "1_1") (pintype "unspecified"))
      (node (ref "R18") (pin "2") (pinfunction "2_2") (pintype "unspecified"))
      (node (ref "U1") (pin "13") (pinfunction "IO14_13") (pintype "unspecified"))
    )
    (net (code "19") (name "IO15") (class "Default")
      (node (ref "R11") (pin "1") (pinfunction "1_1") (pintype "unspecified"))
      (node (ref "R6") (pin "2") (pinfunction "2_2") (pintype "unspecified"))
      (node (ref "U1") (pin "23") (pinfunction "IO15_23") (pintype "unspecified"))
    )
    (net (code "20") (name "IO16") (class "Default")
      (node (ref "R13") (pin "2") (pinfunction "2_2") (pintype "unspecified"))
      (node (ref "R14") (pin "1") (pinfunction "1_1") (pintype "unspecified"))
      (node (ref "U1") (pin "27") (pinfunction "IO16_27") (pintype "unspecified"))
    )
    (net (code "21") (name "IO17") (class "Default")
      (node (ref "R15") (pin "1") (pinfunction "1_1") (pintype "unspecified"))
      (node (ref "R16") (pin "2") (pinfunction "2_2") (pintype "unspecified"))
      (node (ref "U1") (pin "28") (pinfunction "IO17_28") (pintype "unspecified"))
    )
    (net (code "22") (name "IO18") (class "Default")
      (node (ref "R7") (pin "1") (pinfunction "1_1") (pintype "unspecified"))
      (node (ref "U1") (pin "30") (pinfunction "IO18_30") (pintype "unspecified"))
    )
    (net (code "23") (name "IO19") (class "Default")
      (node (ref "R21") (pin "1") (pinfunction "1_1") (pintype "unspecified"))
      (node (ref "U1") (pin "31") (pinfunction "IO19_31") (pintype "unspecified"))
      (node (ref "U18") (pin "2") (pinfunction "SDA_2") (pintype "unspecified"))
    )
    (net (code "24") (name "IO23") (class "Default")
      (node (ref "U1") (pin "37") (pinfunction "IO23_37") (pintype "unspecified"))
      (node (ref "U15") (pin "2") (pinfunction "2_2") (pintype "unspecified"))
    )
    (net (code "25") (name "IO25") (class "Default")
      (node (ref "J14") (pin "1") (pinfunction "1_1") (pintype "unspecified"))
      (node (ref "U1") (pin "10") (pinfunction "IO25_10") (pintype "unspecified"))
    )
    (net (code "26") (name "IO26") (class "Default")
      (node (ref "J15") (pin "1") (pinfunction "1_1") (pintype "unspecified"))
      (node (ref "U1") (pin "11") (pinfunction "IO26_11") (pintype "unspecified"))
    )
    (net (code "27") (name "IO27") (class "Default")
      (node (ref "J16") (pin "1") (pinfunction "1_1") (pintype "unspecified"))
      (node (ref "U1") (pin "12") (pinfunction "IO27_12") (pintype "unspecified"))
    )
    (net (code "28") (name "IO32") (class "Default")
      (node (ref "J12") (pin "1") (pinfunction "1_1") (pintype "unspecified"))
      (node (ref "U1") (pin "8") (pinfunction "IO32_8") (pintype "unspecified"))
    )
    (net (code "29") (name "IO33") (class "Default")
      (node (ref "U1") (pin "9") (pinfunction "IO33_9") (pintype "unspecified"))
      (node (ref "U17") (pin "1") (pinfunction "1_1") (pintype "unspecified"))
    )
    (net (code "30") (name "IO34") (class "Default")
      (node (ref "J10") (pin "1") (pinfunction "1_1") (pintype "unspecified"))
      (node (ref "U1") (pin "6") (pinfunction "IO34_6") (pintype "unspecified"))
    )
    (net (code "31") (name "IO35") (class "Default")
      (node (ref "J11") (pin "1") (pinfunction "1_1") (pintype "unspecified"))
      (node (ref "U1") (pin "7") (pinfunction "IO35_7") (pintype "unspecified"))
    )
    (net (code "32") (name "MCU_PWR") (class "Default")
      (node (ref "C1") (pin "1") (pinfunction "1_1") (pintype "unspecified"))
      (node (ref "C4") (pin "1") (pinfunction "1_1") (pintype "unspecified"))
      (node (ref "SW2") (pin "2") (pinfunction "2_2") (pintype "unspecified"))
      (node (ref "U2") (pin "1") (pinfunction "VIN_1") (pintype "unspecified"))
      (node (ref "U2") (pin "3") (pinfunction "EN_3") (pintype "unspecified"))
      (node (ref "U3") (pin "1") (pinfunction "VIN_1") (pintype "unspecified"))
      (node (ref "U6") (pin "2") (pinfunction "2_2") (pintype "unspecified"))
    )
    (net (code "33") (name "MM_P1") (class "Default")
      (node (ref "C10") (pin "1") (pinfunction "1_1") (pintype "unspecified"))
      (node (ref "U15") (pin "1") (pinfunction "1_1") (pintype "unspecified"))
      (node (ref "U16") (pin "2") (pinfunction "2_2") (pintype "unspecified"))
      (node (ref "U17") (pin "2") (pinfunction "2_2") (pintype "unspecified"))
    )
    (net (code "34") (name "Net-(LED2-+)") (class "Default")
      (node (ref "LED2") (pin "2") (pinfunction "+_2") (pintype "unspecified"))
      (node (ref "R10") (pin "2") (pinfunction "2_2") (pintype "unspecified"))
    )
    (net (code "35") (name "Net-(LED3-A)") (class "Default")
      (node (ref "LED3") (pin "1") (pinfunction "A_1") (pintype "unspecified"))
      (node (ref "R12") (pin "2") (pinfunction "2_2") (pintype "unspecified"))
    )
    (net (code "36") (name "Net-(P1-Pad1)") (class "Default")
      (node (ref "P1") (pin "1") (pinfunction "1_1") (pintype "unspecified"))
      (node (ref "R22") (pin "2") (pinfunction "2_2") (pintype "unspecified"))
      (node (ref "U8") (pin "2") (pinfunction "AC_2") (pintype "unspecified"))
    )
    (net (code "37") (name "Net-(P1-Pad2)") (class "Default")
      (node (ref "P1") (pin "2") (pinfunction "2_2") (pintype "unspecified"))
      (node (ref "R22") (pin "1") (pinfunction "1_1") (pintype "unspecified"))
      (node (ref "U8") (pin "1") (pinfunction "AC_1") (pintype "unspecified"))
    )
    (net (code "38") (name "Net-(Q1-B)") (class "Default")
      (node (ref "Q1") (pin "1") (pinfunction "B_1") (pintype "unspecified"))
      (node (ref "R8") (pin "2") (pinfunction "2_2") (pintype "unspecified"))
    )
    (net (code "39") (name "Net-(Q2-B)") (class "Default")
      (node (ref "Q2") (pin "1") (pinfunction "B_1") (pintype "unspecified"))
      (node (ref "R9") (pin "2") (pinfunction "2_2") (pintype "unspecified"))
    )
    (net (code "40") (name "Net-(R4-Pad1)") (class "Default")
      (node (ref "R4") (pin "1") (pinfunction "1_1") (pintype "unspecified"))
      (node (ref "RL1") (pin "14") (pinfunction "14_14") (pintype "unspecified"))
    )
    (net (code "41") (name "Net-(R5-Pad1)") (class "Default")
      (node (ref "R5") (pin "1") (pinfunction "1_1") (pintype "unspecified"))
      (node (ref "SW1") (pin "2") (pinfunction "2_2") (pintype "unspecified"))
    )
    (net (code "42") (name "Net-(R6-Pad1)") (class "Default")
      (node (ref "R6") (pin "1") (pinfunction "1_1") (pintype "unspecified"))
      (node (ref "RL2") (pin "14") (pinfunction "14_14") (pintype "unspecified"))
    )
    (net (code "43") (name "Net-(R13-Pad1)") (class "Default")
      (node (ref "R13") (pin "1") (pinfunction "1_1") (pintype "unspecified"))
      (node (ref "RL4") (pin "14") (pinfunction "14_14") (pintype "unspecified"))
    )
    (net (code "44") (name "Net-(R16-Pad1)") (class "Default")
      (node (ref "R16") (pin "1") (pinfunction "1_1") (pintype "unspecified"))
      (node (ref "RL3") (pin "14") (pinfunction "14_14") (pintype "unspecified"))
    )
    (net (code "45") (name "Net-(R18-Pad1)") (class "Default")
      (node (ref "R18") (pin "1") (pinfunction "1_1") (pintype "unspecified"))
      (node (ref "U17") (pin "3") (pinfunction "3_3") (pintype "unspecified"))
    )
    (net (code "46") (name "Net-(R19-Pad1)") (class "Default")
      (node (ref "R19") (pin "1") (pinfunction "1_1") (pintype "unspecified"))
      (node (ref "U17") (pin "4") (pinfunction "4_4") (pintype "unspecified"))
    )
    (net (code "47") (name "Net-(U4-A)") (class "Default")
      (node (ref "R7") (pin "2") (pinfunction "2_2") (pintype "unspecified"))
      (node (ref "U4") (pin "1") (pinfunction "A_1") (pintype "unspecified"))
    )
    (net (code "48") (name "RESET") (class "Default")
      (node (ref "C5") (pin "1") (pinfunction "1_1") (pintype "unspecified"))
      (node (ref "Q2") (pin "3") (pinfunction "C_3") (pintype "unspecified"))
      (node (ref "SW1") (pin "1") (pinfunction "1_1") (pintype "unspecified"))
      (node (ref "U1") (pin "3") (pinfunction "EN_3") (pintype "unspecified"))
    )
    (net (code "49") (name "S1") (class "Default")
      (node (ref "U10") (pin "5") (pinfunction "5_5") (pintype "unspecified"))
      (node (ref "U11") (pin "1") (pinfunction "1_1") (pintype "unspecified"))
    )
    (net (code "50") (name "S2") (class "Default")
      (node (ref "U11") (pin "2") (pinfunction "2_2") (pintype "unspecified"))
      (node (ref "U12") (pin "5") (pinfunction "5_5") (pintype "unspecified"))
    )
    (net (code "51") (name "S3") (class "Default")
      (node (ref "U11") (pin "3") (pinfunction "3_3") (pintype "unspecified"))
      (node (ref "U14") (pin "5") (pinfunction "5_5") (pintype "unspecified"))
    )
    (net (code "52") (name "S4") (class "Default")
      (node (ref "U11") (pin "4") (pinfunction "4_4") (pintype "unspecified"))
      (node (ref "U13") (pin "5") (pinfunction "5_5") (pintype "unspecified"))
    )
    (net (code "53") (name "SCL") (class "Default")
      (node (ref "J20") (pin "1") (pinfunction "1_1") (pintype "unspecified"))
      (node (ref "J22") (pin "1") (pinfunction "1_1") (pintype "unspecified"))
      (node (ref "R2") (pin "2") (pinfunction "2_2") (pintype "unspecified"))
      (node (ref "U1") (pin "36") (pinfunction "IO22_36") (pintype "unspecified"))
    )
    (net (code "54") (name "SDA") (class "Default")
      (node (ref "J19") (pin "1") (pinfunction "1_1") (pintype "unspecified"))
      (node (ref "J21") (pin "1") (pinfunction "1_1") (pintype "unspecified"))
      (node (ref "R1") (pin "2") (pinfunction "2_2") (pintype "unspecified"))
      (node (ref "U1") (pin "33") (pinfunction "IO21_33") (pintype "unspecified"))
    )
    (net (code "55") (name "T1_O+") (class "Default")
      (node (ref "RL1") (pin "A1") (pinfunction "A1_A1") (pintype "unspecified"))
      (node (ref "U10") (pin "3") (pinfunction "3_3") (pintype "unspecified"))
    )
    (net (code "56") (name "T1_O-") (class "Default")
      (node (ref "RL1") (pin "A2") (pinfunction "A2_A2") (pintype "unspecified"))
      (node (ref "U10") (pin "4") (pinfunction "4_4") (pintype "unspecified"))
    )
    (net (code "57") (name "T2_O+") (class "Default")
      (node (ref "RL2") (pin "A1") (pinfunction "A1_A1") (pintype "unspecified"))
      (node (ref "U12") (pin "3") (pinfunction "3_3") (pintype "unspecified"))
    )
    (net (code "58") (name "T2_O-") (class "Default")
      (node (ref "RL2") (pin "A2") (pinfunction "A2_A2") (pintype "unspecified"))
      (node (ref "U12") (pin "4") (pinfunction "4_4") (pintype "unspecified"))
    )
    (net (code "59") (name "T3_O+") (class "Default")
      (node (ref "RL4") (pin "A1") (pinfunction "A1_A1") (pintype "unspecified"))
      (node (ref "U14") (pin "3") (pinfunction "3_3") (pintype "unspecified"))
    )
    (net (code "60") (name "T3_O-") (class "Default")
      (node (ref "RL4") (pin "A2") (pinfunction "A2_A2") (pintype "unspecified"))
      (node (ref "U14") (pin "4") (pinfunction "4_4") (pintype "unspecified"))
    )
    (net (code "61") (name "T4_O+") (class "Default")
      (node (ref "RL3") (pin "A1") (pinfunction "A1_A1") (pintype "unspecified"))
      (node (ref "U13") (pin "3") (pinfunction "3_3") (pintype "unspecified"))
    )
    (net (code "62") (name "T4_O-") (class "Default")
      (node (ref "RL3") (pin "A2") (pinfunction "A2_A2") (pintype "unspecified"))
      (node (ref "U13") (pin "4") (pinfunction "4_4") (pintype "unspecified"))
    )
    (net (code "63") (name "USB 5V") (class "Default")
      (node (ref "J1") (pin "1") (pinfunction "1_1") (pintype "unspecified"))
      (node (ref "SW2") (pin "1") (pinfunction "1_1") (pintype "unspecified"))
      (node (ref "U5") (pin "8") (pinfunction "VBUS_8") (pintype "unspecified"))
      (node (ref "USB1") (pin "1") (pinfunction "VBUS_1") (pintype "unspecified"))
    )
    (net (code "64") (name "unconnected-(RL1-Pad12)") (class "Default")
      (node (ref "RL1") (pin "12") (pinfunction "12_12") (pintype "unspecified+no_connect"))
    )
    (net (code "65") (name "unconnected-(RL2-Pad12)") (class "Default")
      (node (ref "RL2") (pin "12") (pinfunction "12_12") (pintype "unspecified+no_connect"))
    )
    (net (code "66") (name "unconnected-(RL3-Pad12)") (class "Default")
      (node (ref "RL3") (pin "12") (pinfunction "12_12") (pintype "unspecified+no_connect"))
    )
    (net (code "67") (name "unconnected-(RL4-Pad12)") (class "Default")
      (node (ref "RL4") (pin "12") (pinfunction "12_12") (pintype "unspecified+no_connect"))
    )
    (net (code "68") (name "unconnected-(SW2-Pad4)") (class "Default")
      (node (ref "SW2") (pin "4") (pinfunction "4_4") (pintype "unspecified+no_connect"))
    )
    (net (code "69") (name "unconnected-(SW2-Pad5)") (class "Default")
      (node (ref "SW2") (pin "5") (pinfunction "5_5") (pintype "unspecified+no_connect"))
    )
    (net (code "70") (name "unconnected-(U1-NC-Pad32)") (class "Default")
      (node (ref "U1") (pin "32") (pinfunction "NC_32") (pintype "unspecified+no_connect"))
    )
    (net (code "71") (name "unconnected-(U1-SCK{slash}CLK-Pad20)") (class "Default")
      (node (ref "U1") (pin "20") (pinfunction "SCK/CLK_20") (pintype "unspecified+no_connect"))
    )
    (net (code "72") (name "unconnected-(U1-SCS{slash}CMD-Pad19)") (class "Default")
      (node (ref "U1") (pin "19") (pinfunction "SCS/CMD_19") (pintype "unspecified+no_connect"))
    )
    (net (code "73") (name "unconnected-(U1-SDI{slash}SD1-Pad22)") (class "Default")
      (node (ref "U1") (pin "22") (pinfunction "SDI/SD1_22") (pintype "unspecified+no_connect"))
    )
    (net (code "74") (name "unconnected-(U1-SDO{slash}SD0-Pad21)") (class "Default")
      (node (ref "U1") (pin "21") (pinfunction "SDO/SD0_21") (pintype "unspecified+no_connect"))
    )
    (net (code "75") (name "unconnected-(U1-SENSOR_VN-Pad5)") (class "Default")
      (node (ref "U1") (pin "5") (pinfunction "SENSOR_VN_5") (pintype "unspecified+no_connect"))
    )
    (net (code "76") (name "unconnected-(U1-SENSOR_VP-Pad4)") (class "Default")
      (node (ref "U1") (pin "4") (pinfunction "SENSOR_VP_4") (pintype "unspecified+no_connect"))
    )
    (net (code "77") (name "unconnected-(U1-SHD{slash}SD2-Pad17)") (class "Default")
      (node (ref "U1") (pin "17") (pinfunction "SHD/SD2_17") (pintype "unspecified+no_connect"))
    )
    (net (code "78") (name "unconnected-(U1-SWP{slash}SD3-Pad18)") (class "Default")
      (node (ref "U1") (pin "18") (pinfunction "SWP/SD3_18") (pintype "unspecified+no_connect"))
    )
    (net (code "79") (name "unconnected-(U2-NC-Pad4)") (class "Default")
      (node (ref "U2") (pin "4") (pinfunction "NC_4") (pintype "unspecified+no_connect"))
    )
    (net (code "80") (name "unconnected-(U3-NC-Pad4)") (class "Default")
      (node (ref "U3") (pin "4") (pinfunction "NC_4") (pintype "unspecified+no_connect"))
    )
    (net (code "81") (name "unconnected-(U5-CTS-Pad18)") (class "Default")
      (node (ref "U5") (pin "18") (pinfunction "CTS_18") (pintype "unspecified+no_connect"))
    )
    (net (code "82") (name "unconnected-(U5-DCD-Pad24)") (class "Default")
      (node (ref "U5") (pin "24") (pinfunction "DCD_24") (pintype "unspecified+no_connect"))
    )
    (net (code "83") (name "unconnected-(U5-DSR-Pad22)") (class "Default")
      (node (ref "U5") (pin "22") (pinfunction "DSR_22") (pintype "unspecified+no_connect"))
    )
    (net (code "84") (name "unconnected-(U5-EPAD-Pad25)") (class "Default")
      (node (ref "U5") (pin "25") (pinfunction "EPAD_25") (pintype "unspecified+no_connect"))
    )
    (net (code "85") (name "unconnected-(U5-GPIO.0-Pad14)") (class "Default")
      (node (ref "U5") (pin "14") (pinfunction "GPIO.0_14") (pintype "unspecified+no_connect"))
    )
    (net (code "86") (name "unconnected-(U5-GPIO.1-Pad13)") (class "Default")
      (node (ref "U5") (pin "13") (pinfunction "GPIO.1_13") (pintype "unspecified+no_connect"))
    )
    (net (code "87") (name "unconnected-(U5-GPIO.2-Pad12)") (class "Default")
      (node (ref "U5") (pin "12") (pinfunction "GPIO.2_12") (pintype "unspecified+no_connect"))
    )
    (net (code "88") (name "unconnected-(U5-GPIO.3-Pad11)") (class "Default")
      (node (ref "U5") (pin "11") (pinfunction "GPIO.3_11") (pintype "unspecified+no_connect"))
    )
    (net (code "89") (name "unconnected-(U5-NC-Pad10)") (class "Default")
      (node (ref "U5") (pin "10") (pinfunction "NC_10") (pintype "unspecified+no_connect"))
    )
    (net (code "90") (name "unconnected-(U5-RI-Pad1)") (class "Default")
      (node (ref "U5") (pin "1") (pinfunction "RI_1") (pintype "unspecified+no_connect"))
    )
    (net (code "91") (name "unconnected-(U5-RST#-Pad9)") (class "Default")
      (node (ref "U5") (pin "9") (pinfunction "RST#_9") (pintype "unspecified+no_connect"))
    )
    (net (code "92") (name "unconnected-(U5-SUSPEND#-Pad15)") (class "Default")
      (node (ref "U5") (pin "15") (pinfunction "SUSPEND#_15") (pintype "unspecified+no_connect"))
    )
    (net (code "93") (name "unconnected-(U5-SUSPEND-Pad17)") (class "Default")
      (node (ref "U5") (pin "17") (pinfunction "SUSPEND_17") (pintype "unspecified+no_connect"))
    )
    (net (code "94") (name "unconnected-(U5-VPP-Pad16)") (class "Default")
      (node (ref "U5") (pin "16") (pinfunction "VPP_16") (pintype "unspecified+no_connect"))
    )
    (net (code "95") (name "unconnected-(U18-SCK-Pad4)") (class "Default")
      (node (ref "U18") (pin "4") (pinfunction "SCK_4") (pintype "unspecified+no_connect"))
    )
    (net (code "96") (name "unconnected-(USB1-ID-Pad4)") (class "Default")
      (node (ref "USB1") (pin "4") (pinfunction "ID_4") (pintype "unspecified+no_connect"))
    )
  )
)
